# 1-Axis_Board_-_Camera_Gantry.net
KiCad netlist of a schematic drawn in EAGLE
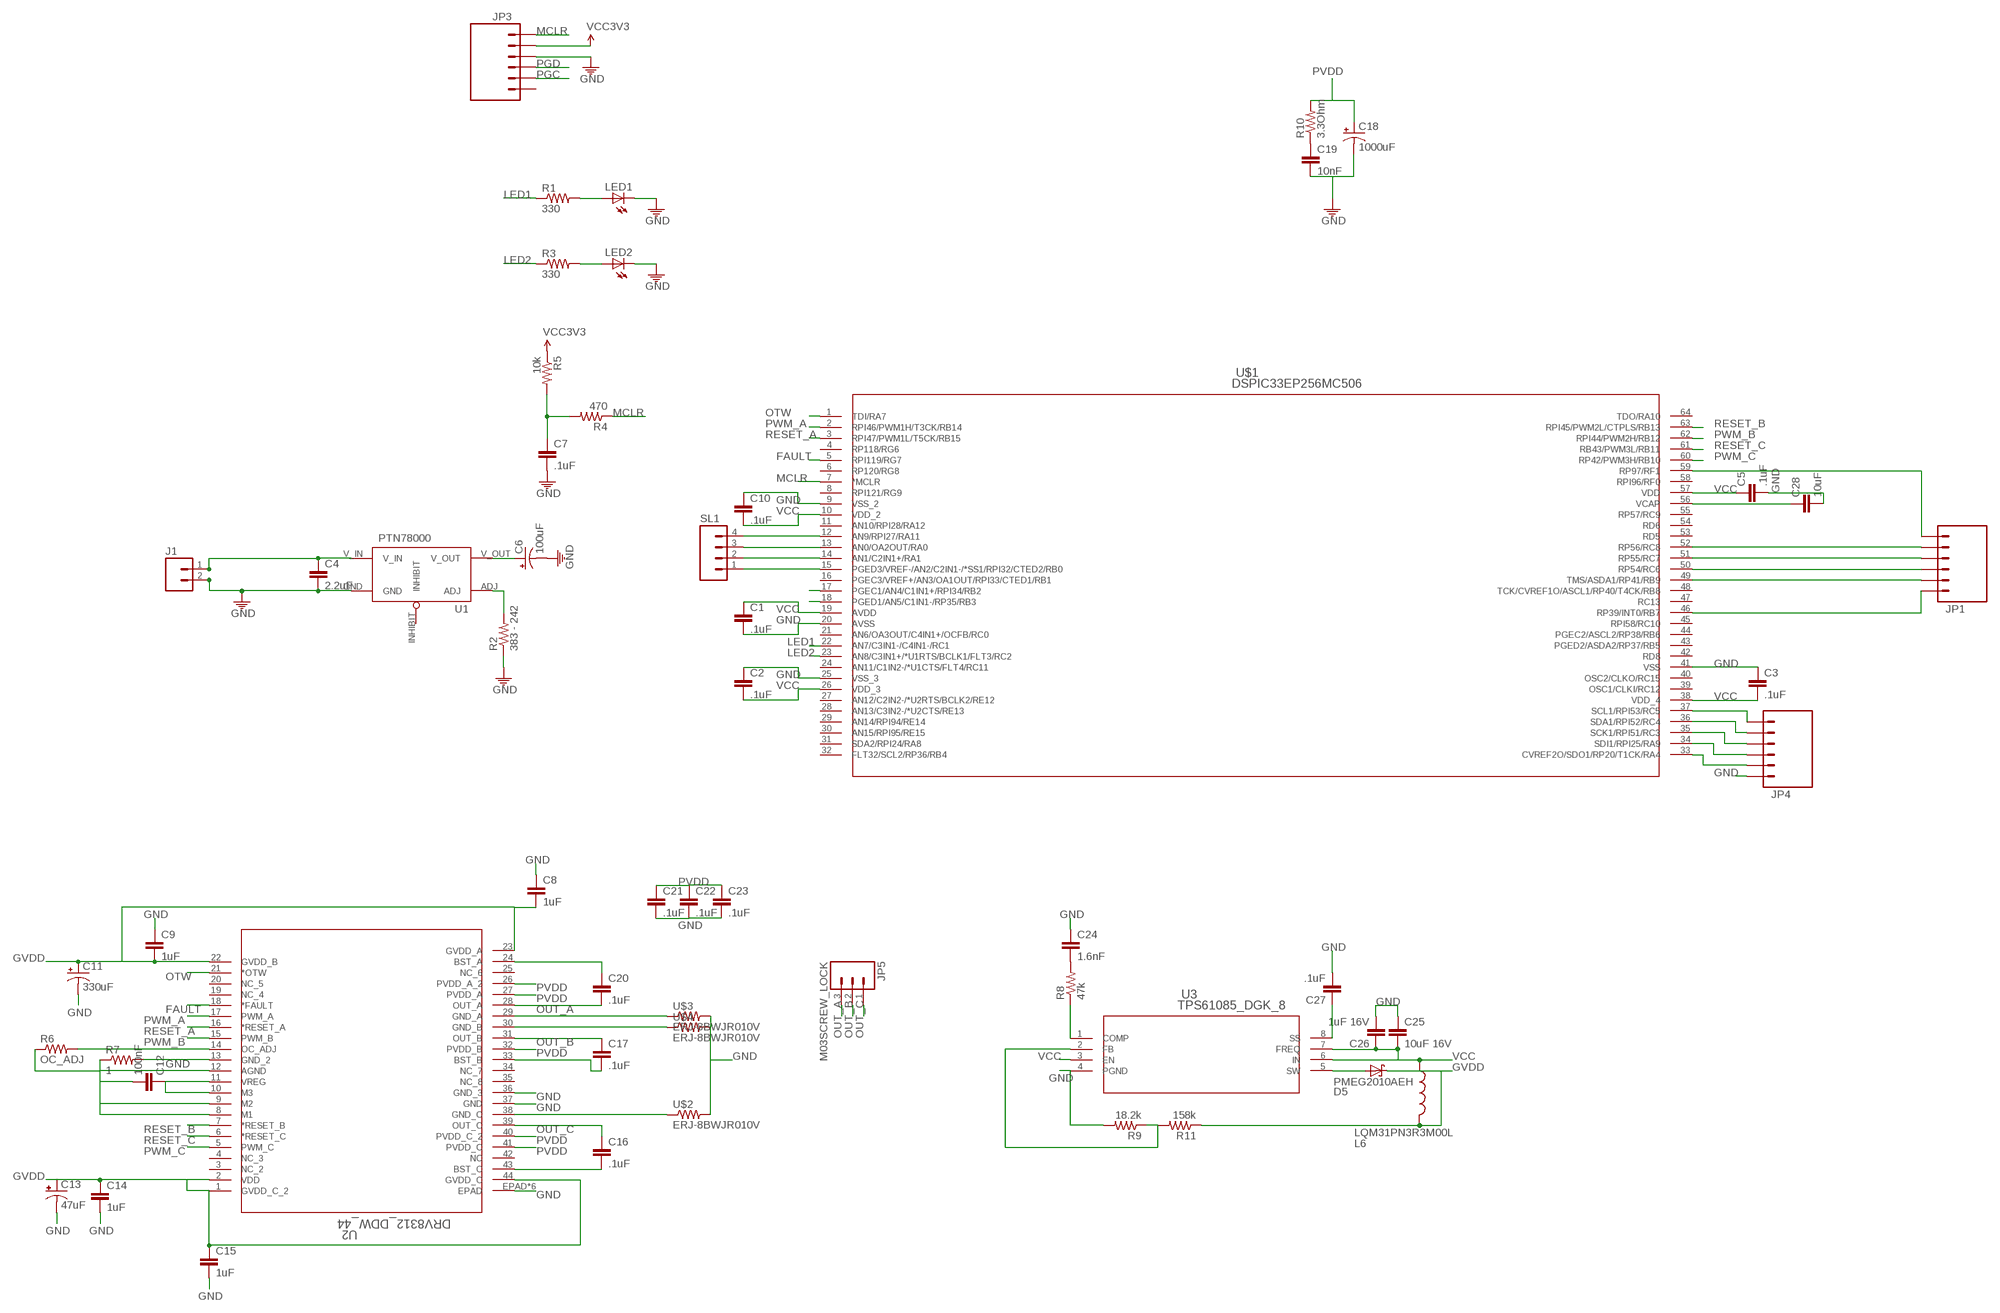
[diagram p0: schematic, sheet 1]

(export (version "E")
  (design (tool "Eeschema 10.0.6"))
  (components
    (comp (ref "C1")
      (value ".1uF")
      (footprint "eagle-import:0805")
      (libsource (lib "eagle-import") (part "CAP0805"))
    )
    (comp (ref "C2")
      (value ".1uF")
      (footprint "eagle-import:0805")
      (libsource (lib "eagle-import") (part "CAP0805"))
    )
    (comp (ref "C3")
      (value ".1uF")
      (footprint "eagle-import:0805")
      (libsource (lib "eagle-import") (part "CAP0805"))
    )
    (comp (ref "C4")
      (value "2.2uF")
      (footprint "eagle-import:1206")
      (libsource (lib "eagle-import") (part "CMPE118lib_CAP1206"))
    )
    (comp (ref "C5")
      (value ".1uF")
      (footprint "eagle-import:0805")
      (libsource (lib "eagle-import") (part "CAP0805"))
    )
    (comp (ref "C6")
      (value "100uF")
      (footprint "eagle-import:CPOL-RADIAL-100UF-25V")
      (libsource (lib "eagle-import") (part "CAP_POLPTH1"))
    )
    (comp (ref "C7")
      (value ".1uF")
      (footprint "eagle-import:0805")
      (libsource (lib "eagle-import") (part "CAP0805"))
    )
    (comp (ref "C8")
      (value "1uF")
      (footprint "eagle-import:0805")
      (libsource (lib "eagle-import") (part "CAP0805"))
    )
    (comp (ref "C9")
      (value "1uF")
      (footprint "eagle-import:0805")
      (libsource (lib "eagle-import") (part "CAP0805"))
    )
    (comp (ref "C10")
      (value ".1uF")
      (footprint "eagle-import:0805")
      (libsource (lib "eagle-import") (part "CAP0805"))
    )
    (comp (ref "C11")
      (value "330uF")
      (footprint "eagle-import:CPOL-RADIAL-1000UF-25V")
      (libsource (lib "eagle-import") (part "CAP_POLPTH4"))
    )
    (comp (ref "C12")
      (value "100nF")
      (footprint "eagle-import:0805")
      (libsource (lib "eagle-import") (part "CAP0805"))
    )
    (comp (ref "C13")
      (value "47uF")
      (footprint "eagle-import:CPOL-RADIAL-1000UF-25V")
      (libsource (lib "eagle-import") (part "CAP_POLPTH4"))
    )
    (comp (ref "C14")
      (value "1uF")
      (footprint "eagle-import:0805")
      (libsource (lib "eagle-import") (part "CAP0805"))
    )
    (comp (ref "C15")
      (value "1uF")
      (footprint "eagle-import:0805")
      (libsource (lib "eagle-import") (part "CAP0805"))
    )
    (comp (ref "C16")
      (value ".1uF")
      (footprint "eagle-import:0805")
      (libsource (lib "eagle-import") (part "CAP0805"))
    )
    (comp (ref "C17")
      (value ".1uF")
      (footprint "eagle-import:0805")
      (libsource (lib "eagle-import") (part "CAP0805"))
    )
    (comp (ref "C18")
      (value "1000uF")
      (footprint "eagle-import:CPOL-RADIAL-1000UF-25V")
      (libsource (lib "eagle-import") (part "CAP_POLPTH4"))
    )
    (comp (ref "C19")
      (value "10nF")
      (footprint "eagle-import:0805")
      (libsource (lib "eagle-import") (part "CAP0805"))
    )
    (comp (ref "C20")
      (value ".1uF")
      (footprint "eagle-import:0805")
      (libsource (lib "eagle-import") (part "CAP0805"))
    )
    (comp (ref "C21")
      (value ".1uF")
      (footprint "eagle-import:0805")
      (libsource (lib "eagle-import") (part "CAP0805"))
    )
    (comp (ref "C22")
      (value ".1uF")
      (footprint "eagle-import:0805")
      (libsource (lib "eagle-import") (part "CAP0805"))
    )
    (comp (ref "C23")
      (value ".1uF")
      (footprint "eagle-import:0805")
      (libsource (lib "eagle-import") (part "CAP0805"))
    )
    (comp (ref "C24")
      (value "1.6nF")
      (footprint "eagle-import:0805")
      (libsource (lib "eagle-import") (part "CAP0805"))
    )
    (comp (ref "C25")
      (value "10uF 16V")
      (footprint "eagle-import:1206")
      (libsource (lib "eagle-import") (part "CAP1206"))
    )
    (comp (ref "C26")
      (value "1uF 16V")
      (footprint "eagle-import:0805")
      (libsource (lib "eagle-import") (part "CAP0805"))
    )
    (comp (ref "C27")
      (value ".1uF")
      (footprint "eagle-import:0805")
      (libsource (lib "eagle-import") (part "CAP0805"))
    )
    (comp (ref "C28")
      (value "10uF")
      (footprint "eagle-import:1206")
      (libsource (lib "eagle-import") (part "CAP1206"))
    )
    (comp (ref "D5")
      (value "PMEG2010AEH")
      (footprint "eagle-import:SOD-123")
      (libsource (lib "eagle-import") (part "PMEG2010AEH"))
    )
    (comp (ref "J1")
      (value "M023.5MM-NO_SILK")
      (footprint "eagle-import:SCREWTERMINAL-3.5MM-2-NS")
      (libsource (lib "eagle-import") (part "M023.5MM-NO_SILK"))
    )
    (comp (ref "JP1")
      (value "M06LOCK")
      (footprint "eagle-import:1X06_LOCK")
      (libsource (lib "eagle-import") (part "M06LOCK"))
    )
    (comp (ref "JP3")
      (value "M06LOCK")
      (footprint "eagle-import:1X06_LOCK")
      (libsource (lib "eagle-import") (part "CMPE118lib_M06LOCK"))
    )
    (comp (ref "JP4")
      (value "M06LOCK")
      (footprint "eagle-import:1X06_LOCK")
      (libsource (lib "eagle-import") (part "M06LOCK"))
    )
    (comp (ref "JP5")
      (value "M03SCREW_LOCK")
      (footprint "eagle-import:SCREWTERMINAL-3.5MM-3_LOCK.007S")
      (libsource (lib "eagle-import") (part "M03SCREW_LOCK"))
    )
    (comp (ref "L6")
      (value "LQM31PN3R3M00L")
      (footprint "eagle-import:1206")
      (libsource (lib "eagle-import") (part "LQM31PN3R3M00L"))
    )
    (comp (ref "LED1")
      (value "LED1206")
      (footprint "eagle-import:LED-1206")
      (fields (field (name "COLOR") "red"))
      (libsource (lib "eagle-import") (part "LED1206"))
    )
    (comp (ref "LED2")
      (value "LED1206")
      (footprint "eagle-import:LED-1206")
      (fields (field (name "COLOR") "red"))
      (libsource (lib "eagle-import") (part "LED1206"))
    )
    (comp (ref "R1")
      (value "330")
      (footprint "eagle-import:0805")
      (libsource (lib "eagle-import") (part "CMPE118lib_RESISTOR0805-RES"))
    )
    (comp (ref "R2")
      (value "383 - 242")
      (footprint "eagle-import:0805")
      (libsource (lib "eagle-import") (part "CMPE118lib_RESISTOR0805-RES"))
    )
    (comp (ref "R3")
      (value "330")
      (footprint "eagle-import:0805")
      (libsource (lib "eagle-import") (part "CMPE118lib_RESISTOR0805-RES"))
    )
    (comp (ref "R4")
      (value "470")
      (footprint "eagle-import:0805")
      (libsource (lib "eagle-import") (part "CMPE118lib_RESISTOR0805-RES"))
    )
    (comp (ref "R5")
      (value "10k")
      (footprint "eagle-import:0805")
      (libsource (lib "eagle-import") (part "CMPE118lib_RESISTOR0805-RES"))
    )
    (comp (ref "R6")
      (value "OC_ADJ")
      (footprint "eagle-import:0805")
      (libsource (lib "eagle-import") (part "RESISTOR0805-RES"))
    )
    (comp (ref "R7")
      (value "1")
      (footprint "eagle-import:0805")
      (libsource (lib "eagle-import") (part "RESISTOR0805-RES"))
    )
    (comp (ref "R8")
      (value "47k")
      (footprint "eagle-import:0805")
      (libsource (lib "eagle-import") (part "RESISTOR0805-RES"))
    )
    (comp (ref "R9")
      (value "18.2k")
      (footprint "eagle-import:0805")
      (libsource (lib "eagle-import") (part "RESISTOR0805-RES"))
    )
    (comp (ref "R10")
      (value "3.3Ohm")
      (footprint "eagle-import:0805")
      (libsource (lib "eagle-import") (part "RESISTOR0805-RES"))
    )
    (comp (ref "R11")
      (value "158k")
      (footprint "eagle-import:0805")
      (libsource (lib "eagle-import") (part "RESISTOR0805-RES"))
    )
    (comp (ref "SL1")
      (value "M04LOCK")
      (footprint "eagle-import:1X04_LOCK")
      (libsource (lib "eagle-import") (part "M04LOCK"))
    )
    (comp (ref "U$1")
      (value "DSPIC33EP256MC506")
      (footprint "eagle-import:QFP64-10X10MC")
      (libsource (lib "eagle-import") (part "DSPIC33EP256MC506"))
    )
    (comp (ref "U$2")
      (value "ERJ-8BWJR010V")
      (footprint "eagle-import:1206")
      (libsource (lib "eagle-import") (part "ERJ-8BWJR010V"))
    )
    (comp (ref "U$3")
      (value "ERJ-8BWJR010V")
      (footprint "eagle-import:1206")
      (libsource (lib "eagle-import") (part "ERJ-8BWJR010V"))
    )
    (comp (ref "U$4")
      (value "ERJ-8BWJR010V")
      (footprint "eagle-import:1206")
      (libsource (lib "eagle-import") (part "ERJ-8BWJR010V"))
    )
    (comp (ref "U1")
      (value "PTN78000")
      (footprint "eagle-import:PTN78000")
      (libsource (lib "eagle-import") (part "PTN78000THROUGH-HOLE"))
    )
    (comp (ref "U2")
      (value "DRV8312_DDW_44")
      (footprint "eagle-import:DDW44_8P26X4P31")
      (fields
        (field (name "GENERIC_PART_NUMBER") "DRV8312")
        (field (name "MANUFACTURER") "Texas Instruments")
        (field (name "MANUFACTURER_PART_NUMBER") "drv8312_ddw_44")
      )
      (libsource (lib "eagle-import") (part "DRV8312_DDW_44"))
    )
    (comp (ref "U3")
      (value "TPS61085_DGK_8")
      (footprint "eagle-import:DGK8")
      (fields
        (field (name "GENERIC_PART_NUMBER") "TPS61085")
        (field (name "MANUFACTURER") "Texas Instruments")
        (field (name "MANUFACTURER_PART_NUMBER") "tps61085_dgk_8")
      )
      (libsource (lib "eagle-import") (part "TPS61085_DGK_8"))
    )
  )
  (nets
    (net (code "1") (name "/FAULT") (class "Default")
      (node (ref "U$1") (pin "5") (pinfunction "RPI119/RG7_5") (pintype "passive"))
      (node (ref "U2") (pin "18") (pinfunction "*FAULT_18") (pintype "output"))
    )
    (net (code "2") (name "/GVDD") (class "Default")
      (node (ref "C11") (pin "1") (pinfunction "+_1") (pintype "passive"))
      (node (ref "C13") (pin "1") (pinfunction "+_1") (pintype "passive"))
      (node (ref "C14") (pin "1") (pinfunction "1_1") (pintype "passive"))
      (node (ref "C15") (pin "1") (pinfunction "1_1") (pintype "passive"))
      (node (ref "C8") (pin "2") (pinfunction "2_2") (pintype "passive"))
      (node (ref "C9") (pin "2") (pinfunction "2_2") (pintype "passive"))
      (node (ref "D5") (pin "C") (pinfunction "C_C") (pintype "passive"))
      (node (ref "L6") (pin "2") (pinfunction "2_2") (pintype "passive"))
      (node (ref "R11") (pin "1") (pinfunction "1_1") (pintype "passive"))
      (node (ref "U2") (pin "1") (pinfunction "GVDD_C_2_1") (pintype "power_in"))
      (node (ref "U2") (pin "2") (pinfunction "VDD_2") (pintype "power_in"))
      (node (ref "U2") (pin "22") (pinfunction "GVDD_B_22") (pintype "power_in"))
      (node (ref "U2") (pin "23") (pinfunction "GVDD_A_23") (pintype "power_in"))
      (node (ref "U2") (pin "44") (pinfunction "GVDD_C_44") (pintype "power_in"))
    )
    (net (code "3") (name "/LED1") (class "Default")
      (node (ref "R1") (pin "1") (pinfunction "1_1") (pintype "passive"))
      (node (ref "U$1") (pin "22") (pinfunction "AN7/C3IN1-/C4IN1-/RC1_22") (pintype "passive"))
    )
    (net (code "4") (name "/LED2") (class "Default")
      (node (ref "R3") (pin "1") (pinfunction "1_1") (pintype "passive"))
      (node (ref "U$1") (pin "23") (pinfunction "AN8/C3IN1+/*U1RTS/BCLK1/FLT3/RC2_23") (pintype "passive"))
    )
    (net (code "5") (name "/MCLR") (class "Default")
      (node (ref "JP3") (pin "1") (pinfunction "1_1") (pintype "passive"))
      (node (ref "R4") (pin "1") (pinfunction "1_1") (pintype "passive"))
      (node (ref "U$1") (pin "7") (pinfunction "*MCLR_7") (pintype "passive"))
    )
    (net (code "6") (name "/OTW") (class "Default")
      (node (ref "U$1") (pin "1") (pinfunction "TDI/RA7_1") (pintype "passive"))
      (node (ref "U2") (pin "21") (pinfunction "*OTW_21") (pintype "output"))
    )
    (net (code "7") (name "/OUT_A") (class "Default")
      (node (ref "C20") (pin "2") (pinfunction "2_2") (pintype "passive"))
      (node (ref "JP5") (pin "3") (pinfunction "3_3") (pintype "passive"))
      (node (ref "U2") (pin "28") (pinfunction "OUT_A_28") (pintype "output"))
    )
    (net (code "8") (name "/OUT_B") (class "Default")
      (node (ref "C17") (pin "1") (pinfunction "1_1") (pintype "passive"))
      (node (ref "JP5") (pin "2") (pinfunction "2_2") (pintype "passive"))
      (node (ref "U2") (pin "31") (pinfunction "OUT_B_31") (pintype "output"))
    )
    (net (code "9") (name "/OUT_C") (class "Default")
      (node (ref "C16") (pin "1") (pinfunction "1_1") (pintype "passive"))
      (node (ref "JP5") (pin "1") (pinfunction "1_1") (pintype "passive"))
      (node (ref "U2") (pin "39") (pinfunction "OUT_C_39") (pintype "output"))
    )
    (net (code "10") (name "/PGC") (class "Default")
      (node (ref "JP3") (pin "5") (pinfunction "5_5") (pintype "passive"))
      (node (ref "U$1") (pin "17") (pinfunction "PGEC1/AN4/C1IN1+/RPI34/RB2_17") (pintype "passive"))
    )
    (net (code "11") (name "/PGD") (class "Default")
      (node (ref "JP3") (pin "4") (pinfunction "4_4") (pintype "passive"))
      (node (ref "U$1") (pin "18") (pinfunction "PGED1/AN5/C1IN1-/RP35/RB3_18") (pintype "passive"))
    )
    (net (code "12") (name "/PVDD") (class "Default")
      (node (ref "C18") (pin "1") (pinfunction "+_1") (pintype "passive"))
      (node (ref "C21") (pin "1") (pinfunction "1_1") (pintype "passive"))
      (node (ref "C22") (pin "1") (pinfunction "1_1") (pintype "passive"))
      (node (ref "C23") (pin "1") (pinfunction "1_1") (pintype "passive"))
      (node (ref "C4") (pin "1") (pinfunction "1_1") (pintype "passive"))
      (node (ref "J1") (pin "1") (pinfunction "2_1") (pintype "passive"))
      (node (ref "R10") (pin "2") (pinfunction "2_2") (pintype "passive"))
      (node (ref "U1") (pin "V_IN") (pinfunction "V_IN_V_IN") (pintype "power_in"))
      (node (ref "U2") (pin "26") (pinfunction "PVDD_A_2_26") (pintype "power_in"))
      (node (ref "U2") (pin "27") (pinfunction "PVDD_A_27") (pintype "power_in"))
      (node (ref "U2") (pin "32") (pinfunction "PVDD_B_32") (pintype "power_in"))
      (node (ref "U2") (pin "40") (pinfunction "PVDD_C_2_40") (pintype "power_in"))
      (node (ref "U2") (pin "41") (pinfunction "PVDD_C_41") (pintype "power_in"))
    )
    (net (code "13") (name "/PWM_A") (class "Default")
      (node (ref "U$1") (pin "2") (pinfunction "RPI46/PWM1H/T3CK/RB14_2") (pintype "passive"))
      (node (ref "U2") (pin "17") (pinfunction "PWM_A_17") (pintype "input"))
    )
    (net (code "14") (name "/PWM_B") (class "Default")
      (node (ref "U$1") (pin "62") (pinfunction "RPI44/PWM2H/RB12_62") (pintype "passive"))
      (node (ref "U2") (pin "15") (pinfunction "PWM_B_15") (pintype "input"))
    )
    (net (code "15") (name "/PWM_C") (class "Default")
      (node (ref "U$1") (pin "60") (pinfunction "RP42/PWM3H/RB10_60") (pintype "passive"))
      (node (ref "U2") (pin "5") (pinfunction "PWM_C_5") (pintype "input"))
    )
    (net (code "16") (name "/RESET_A") (class "Default")
      (node (ref "U$1") (pin "3") (pinfunction "RPI47/PWM1L/T5CK/RB15_3") (pintype "passive"))
      (node (ref "U2") (pin "16") (pinfunction "*RESET_A_16") (pintype "input"))
    )
    (net (code "17") (name "/RESET_B") (class "Default")
      (node (ref "U$1") (pin "63") (pinfunction "RPI45/PWM2L/CTPLS/RB13_63") (pintype "passive"))
      (node (ref "U2") (pin "7") (pinfunction "*RESET_B_7") (pintype "input"))
    )
    (net (code "18") (name "/RESET_C") (class "Default")
      (node (ref "U$1") (pin "61") (pinfunction "RB43/PWM3L/RB11_61") (pintype "passive"))
      (node (ref "U2") (pin "6") (pinfunction "*RESET_C_6") (pintype "input"))
    )
    (net (code "19") (name "/VCC") (class "Default")
      (node (ref "C1") (pin "1") (pinfunction "1_1") (pintype "passive"))
      (node (ref "C10") (pin "2") (pinfunction "2_2") (pintype "passive"))
      (node (ref "C2") (pin "2") (pinfunction "2_2") (pintype "passive"))
      (node (ref "C25") (pin "2") (pinfunction "2_2") (pintype "passive"))
      (node (ref "C26") (pin "1") (pinfunction "1_1") (pintype "passive"))
      (node (ref "C3") (pin "2") (pinfunction "2_2") (pintype "passive"))
      (node (ref "C5") (pin "1") (pinfunction "1_1") (pintype "passive"))
      (node (ref "C6") (pin "1") (pinfunction "+_1") (pintype "passive"))
      (node (ref "L6") (pin "1") (pinfunction "1_1") (pintype "passive"))
      (node (ref "U$1") (pin "10") (pinfunction "VDD_2_10") (pintype "passive"))
      (node (ref "U$1") (pin "19") (pinfunction "AVDD_19") (pintype "passive"))
      (node (ref "U$1") (pin "26") (pinfunction "VDD_3_26") (pintype "passive"))
      (node (ref "U$1") (pin "38") (pinfunction "VDD_4_38") (pintype "passive"))
      (node (ref "U$1") (pin "57") (pinfunction "VDD_57") (pintype "passive"))
      (node (ref "U1") (pin "V_OUT") (pinfunction "V_OUT_V_OUT") (pintype "output"))
      (node (ref "U3") (pin "3") (pinfunction "EN_3") (pintype "input"))
      (node (ref "U3") (pin "6") (pinfunction "IN_6") (pintype "input"))
      (node (ref "U3") (pin "7") (pinfunction "FREQ_7") (pintype "input"))
    )
    (net (code "20") (name "GND") (class "Default")
      (node (ref "C1") (pin "2") (pinfunction "2_2") (pintype "passive"))
      (node (ref "C10") (pin "1") (pinfunction "1_1") (pintype "passive"))
      (node (ref "C11") (pin "2") (pinfunction "-_2") (pintype "passive"))
      (node (ref "C13") (pin "2") (pinfunction "-_2") (pintype "passive"))
      (node (ref "C14") (pin "2") (pinfunction "2_2") (pintype "passive"))
      (node (ref "C15") (pin "2") (pinfunction "2_2") (pintype "passive"))
      (node (ref "C18") (pin "2") (pinfunction "-_2") (pintype "passive"))
      (node (ref "C19") (pin "2") (pinfunction "2_2") (pintype "passive"))
      (node (ref "C2") (pin "1") (pinfunction "1_1") (pintype "passive"))
      (node (ref "C21") (pin "2") (pinfunction "2_2") (pintype "passive"))
      (node (ref "C22") (pin "2") (pinfunction "2_2") (pintype "passive"))
      (node (ref "C23") (pin "2") (pinfunction "2_2") (pintype "passive"))
      (node (ref "C24") (pin "1") (pinfunction "1_1") (pintype "passive"))
      (node (ref "C25") (pin "1") (pinfunction "1_1") (pintype "passive"))
      (node (ref "C26") (pin "2") (pinfunction "2_2") (pintype "passive"))
      (node (ref "C27") (pin "2") (pinfunction "2_2") (pintype "passive"))
      (node (ref "C28") (pin "2") (pinfunction "2_2") (pintype "passive"))
      (node (ref "C3") (pin "1") (pinfunction "1_1") (pintype "passive"))
      (node (ref "C4") (pin "2") (pinfunction "2_2") (pintype "passive"))
      (node (ref "C5") (pin "2") (pinfunction "2_2") (pintype "passive"))
      (node (ref "C6") (pin "2") (pinfunction "-_2") (pintype "passive"))
      (node (ref "C7") (pin "2") (pinfunction "2_2") (pintype "passive"))
      (node (ref "C8") (pin "1") (pinfunction "1_1") (pintype "passive"))
      (node (ref "C9") (pin "1") (pinfunction "1_1") (pintype "passive"))
      (node (ref "J1") (pin "2") (pinfunction "1_2") (pintype "passive"))
      (node (ref "JP3") (pin "3") (pinfunction "3_3") (pintype "passive"))
      (node (ref "JP4") (pin "1") (pinfunction "1_1") (pintype "passive"))
      (node (ref "LED1") (pin "C") (pinfunction "C_C") (pintype "passive"))
      (node (ref "LED2") (pin "C") (pinfunction "C_C") (pintype "passive"))
      (node (ref "R2") (pin "1") (pinfunction "1_1") (pintype "passive"))
      (node (ref "R7") (pin "2") (pinfunction "2_2") (pintype "passive"))
      (node (ref "R9") (pin "2") (pinfunction "2_2") (pintype "passive"))
      (node (ref "U$1") (pin "20") (pinfunction "AVSS_20") (pintype "passive"))
      (node (ref "U$1") (pin "25") (pinfunction "VSS_3_25") (pintype "passive"))
      (node (ref "U$1") (pin "41") (pinfunction "VSS_41") (pintype "passive"))
      (node (ref "U$1") (pin "9") (pinfunction "VSS_2_9") (pintype "passive"))
      (node (ref "U$2") (pin "2") (pinfunction "2_2") (pintype "passive"))
      (node (ref "U$3") (pin "2") (pinfunction "2_2") (pintype "passive"))
      (node (ref "U$4") (pin "2") (pinfunction "2_2") (pintype "passive"))
      (node (ref "U1") (pin "GND") (pinfunction "GND_GND") (pintype "power_in"))
      (node (ref "U2") (pin "13") (pinfunction "GND_2_13") (pintype "power_in"))
      (node (ref "U2") (pin "36") (pinfunction "GND_3_36") (pintype "power_in"))
      (node (ref "U2") (pin "37") (pinfunction "GND_37") (pintype "power_in"))
      (node (ref "U2") (pin "EPAD") (pinfunction "EPAD_EPAD") (pintype "passive"))
      (node (ref "U2") (pin "P$1") (pinfunction "EPAD_P$1") (pintype "passive"))
      (node (ref "U2") (pin "P$2") (pinfunction "EPAD_P$2") (pintype "passive"))
      (node (ref "U2") (pin "P$3") (pinfunction "EPAD_P$3") (pintype "passive"))
      (node (ref "U2") (pin "P$7") (pinfunction "EPAD_P$7") (pintype "passive"))
      (node (ref "U2") (pin "P$8") (pinfunction "EPAD_P$8") (pintype "passive"))
      (node (ref "U3") (pin "4") (pinfunction "PGND_4") (pintype "power_in"))
    )
    (net (code "21") (name "Net-(C7-Pad1)") (class "Default")
      (node (ref "C7") (pin "1") (pinfunction "1_1") (pintype "passive"))
      (node (ref "R4") (pin "2") (pinfunction "2_2") (pintype "passive"))
      (node (ref "R5") (pin "2") (pinfunction "2_2") (pintype "passive"))
    )
    (net (code "22") (name "Net-(C19-Pad1)") (class "Default")
      (node (ref "C19") (pin "1") (pinfunction "1_1") (pintype "passive"))
      (node (ref "R10") (pin "1") (pinfunction "1_1") (pintype "passive"))
    )
    (net (code "23") (name "Net-(C24-Pad2)") (class "Default")
      (node (ref "C24") (pin "2") (pinfunction "2_2") (pintype "passive"))
      (node (ref "R8") (pin "2") (pinfunction "2_2") (pintype "passive"))
    )
    (net (code "24") (name "Net-(LED1-PadA)") (class "Default")
      (node (ref "LED1") (pin "A") (pinfunction "A_A") (pintype "passive"))
      (node (ref "R1") (pin "2") (pinfunction "2_2") (pintype "passive"))
    )
    (net (code "25") (name "Net-(LED2-PadA)") (class "Default")
      (node (ref "LED2") (pin "A") (pinfunction "A_A") (pintype "passive"))
      (node (ref "R3") (pin "2") (pinfunction "2_2") (pintype "passive"))
    )
    (net (code "26") (name "Net-(R2-Pad2)") (class "Default")
      (node (ref "R2") (pin "2") (pinfunction "2_2") (pintype "passive"))
      (node (ref "U1") (pin "ADJ") (pinfunction "ADJ_ADJ") (pintype "input"))
    )
    (net (code "27") (name "Net-(U$1-AN0{slash}OA2OUT{slash}RA0)") (class "Default")
      (node (ref "SL1") (pin "3") (pinfunction "3_3") (pintype "passive"))
      (node (ref "U$1") (pin "13") (pinfunction "AN0/OA2OUT/RA0_13") (pintype "passive"))
    )
    (net (code "28") (name "Net-(U$1-AN1{slash}C2IN1+{slash}RA1)") (class "Default")
      (node (ref "SL1") (pin "2") (pinfunction "2_2") (pintype "passive"))
      (node (ref "U$1") (pin "14") (pinfunction "AN1/C2IN1+/RA1_14") (pintype "passive"))
    )
    (net (code "29") (name "Net-(U$1-AN9{slash}RPI27{slash}RA11)") (class "Default")
      (node (ref "SL1") (pin "4") (pinfunction "4_4") (pintype "passive"))
      (node (ref "U$1") (pin "12") (pinfunction "AN9/RPI27/RA11_12") (pintype "passive"))
    )
    (net (code "30") (name "Net-(U$1-CVREF2O{slash}SDO1{slash}RP20{slash}T1CK{slash}RA4)") (class "Default")
      (node (ref "JP4") (pin "2") (pinfunction "2_2") (pintype "passive"))
      (node (ref "U$1") (pin "33") (pinfunction "CVREF2O/SDO1/RP20/T1CK/RA4_33") (pintype "passive"))
    )
    (net (code "31") (name "Net-(U$1-PGED3{slash}VREF-{slash}AN2{slash}C2IN1-{slash}*SS1{slash}RPI32{slash}CTED2{slash}RB0)") (class "Default")
      (node (ref "SL1") (pin "1") (pinfunction "1_1") (pintype "passive"))
      (node (ref "U$1") (pin "15") (pinfunction "PGED3/VREF-/AN2/C2IN1-/*SS1/RPI32/CTED2/RB0_15") (pintype "passive"))
    )
    (net (code "32") (name "Net-(U$1-RP39{slash}INT0{slash}RB7)") (class "Default")
      (node (ref "JP1") (pin "1") (pinfunction "1_1") (pintype "passive"))
      (node (ref "U$1") (pin "46") (pinfunction "RP39/INT0/RB7_46") (pintype "passive"))
    )
    (net (code "33") (name "Net-(U$1-RP54{slash}RC6)") (class "Default")
      (node (ref "JP1") (pin "3") (pinfunction "3_3") (pintype "passive"))
      (node (ref "U$1") (pin "50") (pinfunction "RP54/RC6_50") (pintype "passive"))
    )
    (net (code "34") (name "Net-(U$1-RP55{slash}RC7)") (class "Default")
      (node (ref "JP1") (pin "4") (pinfunction "4_4") (pintype "passive"))
      (node (ref "U$1") (pin "51") (pinfunction "RP55/RC7_51") (pintype "passive"))
    )
    (net (code "35") (name "Net-(U$1-RP56{slash}RC8)") (class "Default")
      (node (ref "JP1") (pin "5") (pinfunction "5_5") (pintype "passive"))
      (node (ref "U$1") (pin "52") (pinfunction "RP56/RC8_52") (pintype "passive"))
    )
    (net (code "36") (name "Net-(U$1-RP97{slash}RF1)") (class "Default")
      (node (ref "JP1") (pin "6") (pinfunction "6_6") (pintype "passive"))
      (node (ref "U$1") (pin "59") (pinfunction "RP97/RF1_59") (pintype "passive"))
    )
    (net (code "37") (name "Net-(U$1-SCK1{slash}RPI51{slash}RC3)") (class "Default")
      (node (ref "JP4") (pin "4") (pinfunction "4_4") (pintype "passive"))
      (node (ref "U$1") (pin "35") (pinfunction "SCK1/RPI51/RC3_35") (pintype "passive"))
    )
    (net (code "38") (name "Net-(U$1-SCL1{slash}RPI53{slash}RC5)") (class "Default")
      (node (ref "JP4") (pin "6") (pinfunction "6_6") (pintype "passive"))
      (node (ref "U$1") (pin "37") (pinfunction "SCL1/RPI53/RC5_37") (pintype "passive"))
    )
    (net (code "39") (name "Net-(U$1-SDA1{slash}RPI52{slash}RC4)") (class "Default")
      (node (ref "JP4") (pin "5") (pinfunction "5_5") (pintype "passive"))
      (node (ref "U$1") (pin "36") (pinfunction "SDA1/RPI52/RC4_36") (pintype "passive"))
    )
    (net (code "40") (name "Net-(U$1-SDI1{slash}RPI25{slash}RA9)") (class "Default")
      (node (ref "JP4") (pin "3") (pinfunction "3_3") (pintype "passive"))
      (node (ref "U$1") (pin "34") (pinfunction "SDI1/RPI25/RA9_34") (pintype "passive"))
    )
    (net (code "41") (name "Net-(U$1-TMS{slash}ASDA1{slash}RP41{slash}RB9)") (class "Default")
      (node (ref "JP1") (pin "2") (pinfunction "2_2") (pintype "passive"))
      (node (ref "U$1") (pin "49") (pinfunction "TMS/ASDA1/RP41/RB9_49") (pintype "passive"))
    )
    (net (code "42") (name "Net-(U$1-VCAP)") (class "Default")
      (node (ref "C28") (pin "1") (pinfunction "1_1") (pintype "passive"))
      (node (ref "U$1") (pin "56") (pinfunction "VCAP_56") (pintype "passive"))
    )
    (net (code "43") (name "Net-(U2-AGND)") (class "Default")
      (node (ref "C12") (pin "2") (pinfunction "2_2") (pintype "passive"))
      (node (ref "R6") (pin "1") (pinfunction "1_1") (pintype "passive"))
      (node (ref "R7") (pin "1") (pinfunction "1_1") (pintype "passive"))
      (node (ref "U2") (pin "12") (pinfunction "AGND_12") (pintype "power_in"))
      (node (ref "U2") (pin "8") (pinfunction "M1_8") (pintype "input"))
      (node (ref "U2") (pin "9") (pinfunction "M2_9") (pintype "input"))
    )
    (net (code "44") (name "Net-(U2-BST_A)") (class "Default")
      (node (ref "C20") (pin "1") (pinfunction "1_1") (pintype "passive"))
      (node (ref "U2") (pin "24") (pinfunction "BST_A_24") (pintype "power_in"))
    )
    (net (code "45") (name "Net-(U2-BST_B)") (class "Default")
      (node (ref "C17") (pin "2") (pinfunction "2_2") (pintype "passive"))
      (node (ref "U2") (pin "33") (pinfunction "BST_B_33") (pintype "power_in"))
    )
    (net (code "46") (name "Net-(U2-BST_C)") (class "Default")
      (node (ref "C16") (pin "2") (pinfunction "2_2") (pintype "passive"))
      (node (ref "U2") (pin "43") (pinfunction "BST_C_43") (pintype "power_in"))
    )
    (net (code "47") (name "Net-(U2-GND_A)") (class "Default")
      (node (ref "U$3") (pin "1") (pinfunction "1_1") (pintype "passive"))
      (node (ref "U2") (pin "29") (pinfunction "GND_A_29") (pintype "power_in"))
    )
    (net (code "48") (name "Net-(U2-GND_B)") (class "Default")
      (node (ref "U$4") (pin "1") (pinfunction "1_1") (pintype "passive"))
      (node (ref "U2") (pin "30") (pinfunction "GND_B_30") (pintype "power_in"))
    )
    (net (code "49") (name "Net-(U2-GND_C)") (class "Default")
      (node (ref "U$2") (pin "1") (pinfunction "1_1") (pintype "passive"))
      (node (ref "U2") (pin "38") (pinfunction "GND_C_38") (pintype "power_in"))
    )
    (net (code "50") (name "Net-(U2-M3)") (class "Default")
      (node (ref "C12") (pin "1") (pinfunction "1_1") (pintype "passive"))
      (node (ref "U2") (pin "10") (pinfunction "M3_10") (pintype "input"))
      (node (ref "U2") (pin "11") (pinfunction "VREG_11") (pintype "power_in"))
    )
    (net (code "51") (name "Net-(U2-OC_ADJ)") (class "Default")
      (node (ref "R6") (pin "2") (pinfunction "2_2") (pintype "passive"))
      (node (ref "U2") (pin "14") (pinfunction "OC_ADJ_14") (pintype "output"))
    )
    (net (code "52") (name "Net-(U3-COMP)") (class "Default")
      (node (ref "R8") (pin "1") (pinfunction "1_1") (pintype "passive"))
      (node (ref "U3") (pin "1") (pinfunction "COMP_1") (pintype "passive"))
    )
    (net (code "53") (name "Net-(U3-FB)") (class "Default")
      (node (ref "R11") (pin "2") (pinfunction "2_2") (pintype "passive"))
      (node (ref "R9") (pin "1") (pinfunction "1_1") (pintype "passive"))
      (node (ref "U3") (pin "2") (pinfunction "FB_2") (pintype "input"))
    )
    (net (code "54") (name "Net-(U3-SS)") (class "Default")
      (node (ref "C27") (pin "1") (pinfunction "1_1") (pintype "passive"))
      (node (ref "U3") (pin "8") (pinfunction "SS_8") (pintype "passive"))
    )
    (net (code "55") (name "Net-(U3-SW)") (class "Default")
      (node (ref "D5") (pin "A") (pinfunction "A_A") (pintype "passive"))
      (node (ref "U3") (pin "5") (pinfunction "SW_5") (pintype "passive"))
    )
    (net (code "56") (name "VCC3V3") (class "Default")
      (node (ref "JP3") (pin "2") (pinfunction "2_2") (pintype "passive"))
      (node (ref "R5") (pin "1") (pinfunction "1_1") (pintype "passive"))
    )
    (net (code "57") (name "unconnected-(JP3-Pad6)") (class "Default")
      (node (ref "JP3") (pin "6") (pinfunction "6_6") (pintype "passive"))
    )
    (net (code "58") (name "unconnected-(U$1-AN6{slash}OA3OUT{slash}C4IN1+{slash}OCFB{slash}RC0-Pad21)") (class "Default")
      (node (ref "U$1") (pin "21") (pinfunction "AN6/OA3OUT/C4IN1+/OCFB/RC0_21") (pintype "passive"))
    )
    (net (code "59") (name "unconnected-(U$1-AN10{slash}RPI28{slash}RA12-Pad11)") (class "Default")
      (node (ref "U$1") (pin "11") (pinfunction "AN10/RPI28/RA12_11") (pintype "passive"))
    )
    (net (code "60") (name "unconnected-(U$1-AN11{slash}C1IN2-{slash}*U1CTS{slash}FLT4{slash}RC11-Pad24)") (class "Default")
      (node (ref "U$1") (pin "24") (pinfunction "AN11/C1IN2-/*U1CTS/FLT4/RC11_24") (pintype "passive"))
    )
    (net (code "61") (name "unconnected-(U$1-AN12{slash}C2IN2-{slash}*U2RTS{slash}BCLK2{slash}RE12-Pad27)") (class "Default")
      (node (ref "U$1") (pin "27") (pinfunction "AN12/C2IN2-/*U2RTS/BCLK2/RE12_27") (pintype "passive"))
    )
    (net (code "62") (name "unconnected-(U$1-AN13{slash}C3IN2-{slash}*U2CTS{slash}RE13-Pad28)") (class "Default")
      (node (ref "U$1") (pin "28") (pinfunction "AN13/C3IN2-/*U2CTS/RE13_28") (pintype "passive"))
    )
    (net (code "63") (name "unconnected-(U$1-AN14{slash}RPI94{slash}RE14-Pad29)") (class "Default")
      (node (ref "U$1") (pin "29") (pinfunction "AN14/RPI94/RE14_29") (pintype "passive"))
    )
    (net (code "64") (name "unconnected-(U$1-AN15{slash}RPI95{slash}RE15-Pad30)") (class "Default")
      (node (ref "U$1") (pin "30") (pinfunction "AN15/RPI95/RE15_30") (pintype "passive"))
    )
    (net (code "65") (name "unconnected-(U$1-FLT32{slash}SCL2{slash}RP36{slash}RB4-Pad32)") (class "Default")
      (node (ref "U$1") (pin "32") (pinfunction "FLT32/SCL2/RP36/RB4_32") (pintype "passive"))
    )
    (net (code "66") (name "unconnected-(U$1-OSC1{slash}CLKI{slash}RC12-Pad39)") (class "Default")
      (node (ref "U$1") (pin "39") (pinfunction "OSC1/CLKI/RC12_39") (pintype "passive"))
    )
    (net (code "67") (name "unconnected-(U$1-OSC2{slash}CLKO{slash}RC15-Pad40)") (class "Default")
      (node (ref "U$1") (pin "40") (pinfunction "OSC2/CLKO/RC15_40") (pintype "passive"))
    )
    (net (code "68") (name "unconnected-(U$1-PGEC2{slash}ASCL2{slash}RP38{slash}RB6-Pad44)") (class "Default")
      (node (ref "U$1") (pin "44") (pinfunction "PGEC2/ASCL2/RP38/RB6_44") (pintype "passive"))
    )
    (net (code "69") (name "unconnected-(U$1-PGEC3{slash}VREF+{slash}AN3{slash}OA1OUT{slash}RPI33{slash}CTED1{slash}RB1-Pad16)") (class "Default")
      (node (ref "U$1") (pin "16") (pinfunction "PGEC3/VREF+/AN3/OA1OUT/RPI33/CTED1/RB1_16") (pintype "passive"))
    )
    (net (code "70") (name "unconnected-(U$1-PGED2{slash}ASDA2{slash}RP37{slash}RB5-Pad43)") (class "Default")
      (node (ref "U$1") (pin "43") (pinfunction "PGED2/ASDA2/RP37/RB5_43") (pintype "passive"))
    )
    (net (code "71") (name "unconnected-(U$1-RC13-Pad47)") (class "Default")
      (node (ref "U$1") (pin "47") (pinfunction "RC13_47") (pintype "passive"))
    )
    (net (code "72") (name "unconnected-(U$1-RD5-Pad53)") (class "Default")
      (node (ref "U$1") (pin "53") (pinfunction "RD5_53") (pintype "passive"))
    )
    (net (code "73") (name "unconnected-(U$1-RD6-Pad54)") (class "Default")
      (node (ref "U$1") (pin "54") (pinfunction "RD6_54") (pintype "passive"))
    )
    (net (code "74") (name "unconnected-(U$1-RD8-Pad42)") (class "Default")
      (node (ref "U$1") (pin "42") (pinfunction "RD8_42") (pintype "passive"))
    )
    (net (code "75") (name "unconnected-(U$1-RP57{slash}RC9-Pad55)") (class "Default")
      (node (ref "U$1") (pin "55") (pinfunction "RP57/RC9_55") (pintype "passive"))
    )
    (net (code "76") (name "unconnected-(U$1-RP118{slash}RG6-Pad4)") (class "Default")
      (node (ref "U$1") (pin "4") (pinfunction "RP118/RG6_4") (pintype "passive"))
    )
    (net (code "77") (name "unconnected-(U$1-RP120{slash}RG8-Pad6)") (class "Default")
      (node (ref "U$1") (pin "6") (pinfunction "RP120/RG8_6") (pintype "passive"))
    )
    (net (code "78") (name "unconnected-(U$1-RPI58{slash}RC10-Pad45)") (class "Default")
      (node (ref "U$1") (pin "45") (pinfunction "RPI58/RC10_45") (pintype "passive"))
    )
    (net (code "79") (name "unconnected-(U$1-RPI96{slash}RF0-Pad58)") (class "Default")
      (node (ref "U$1") (pin "58") (pinfunction "RPI96/RF0_58") (pintype "passive"))
    )
    (net (code "80") (name "unconnected-(U$1-RPI121{slash}RG9-Pad8)") (class "Default")
      (node (ref "U$1") (pin "8") (pinfunction "RPI121/RG9_8") (pintype "passive"))
    )
    (net (code "81") (name "unconnected-(U$1-SDA2{slash}RPI24{slash}RA8-Pad31)") (class "Default")
      (node (ref "U$1") (pin "31") (pinfunction "SDA2/RPI24/RA8_31") (pintype "passive"))
    )
    (net (code "82") (name "unconnected-(U$1-TCK{slash}CVREF1O{slash}ASCL1{slash}RP40{slash}T4CK{slash}RB8-Pad48)") (class "Default")
      (node (ref "U$1") (pin "48") (pinfunction "TCK/CVREF1O/ASCL1/RP40/T4CK/RB8_48") (pintype "passive"))
    )
    (net (code "83") (name "unconnected-(U$1-TDO{slash}RA10-Pad64)") (class "Default")
      (node (ref "U$1") (pin "64") (pinfunction "TDO/RA10_64") (pintype "passive"))
    )
    (net (code "84") (name "unconnected-(U1-PadINHIBIT)") (class "Default")
      (node (ref "U1") (pin "INHIBIT") (pinfunction "INHIBIT_INHIBIT") (pintype "input"))
    )
    (net (code "85") (name "unconnected-(U2-NC-Pad42)") (class "Default")
      (node (ref "U2") (pin "42") (pinfunction "NC_42") (pintype "passive"))
    )
    (net (code "86") (name "unconnected-(U2-NC_2-Pad3)") (class "Default")
      (node (ref "U2") (pin "3") (pinfunction "NC_2_3") (pintype "passive"))
    )
    (net (code "87") (name "unconnected-(U2-NC_3-Pad4)") (class "Default")
      (node (ref "U2") (pin "4") (pinfunction "NC_3_4") (pintype "passive"))
    )
    (net (code "88") (name "unconnected-(U2-NC_4-Pad19)") (class "Default")
      (node (ref "U2") (pin "19") (pinfunction "NC_4_19") (pintype "passive"))
    )
    (net (code "89") (name "unconnected-(U2-NC_5-Pad20)") (class "Default")
      (node (ref "U2") (pin "20") (pinfunction "NC_5_20") (pintype "passive"))
    )
    (net (code "90") (name "unconnected-(U2-NC_6-Pad25)") (class "Default")
      (node (ref "U2") (pin "25") (pinfunction "NC_6_25") (pintype "passive"))
    )
    (net (code "91") (name "unconnected-(U2-NC_7-Pad34)") (class "Default")
      (node (ref "U2") (pin "34") (pinfunction "NC_7_34") (pintype "passive"))
    )
    (net (code "92") (name "unconnected-(U2-NC_8-Pad35)") (class "Default")
      (node (ref "U2") (pin "35") (pinfunction "NC_8_35") (pintype "passive"))
    )
  )
)
